# serial_max232.net
KiCad netlist of a schematic drawn in EAGLE
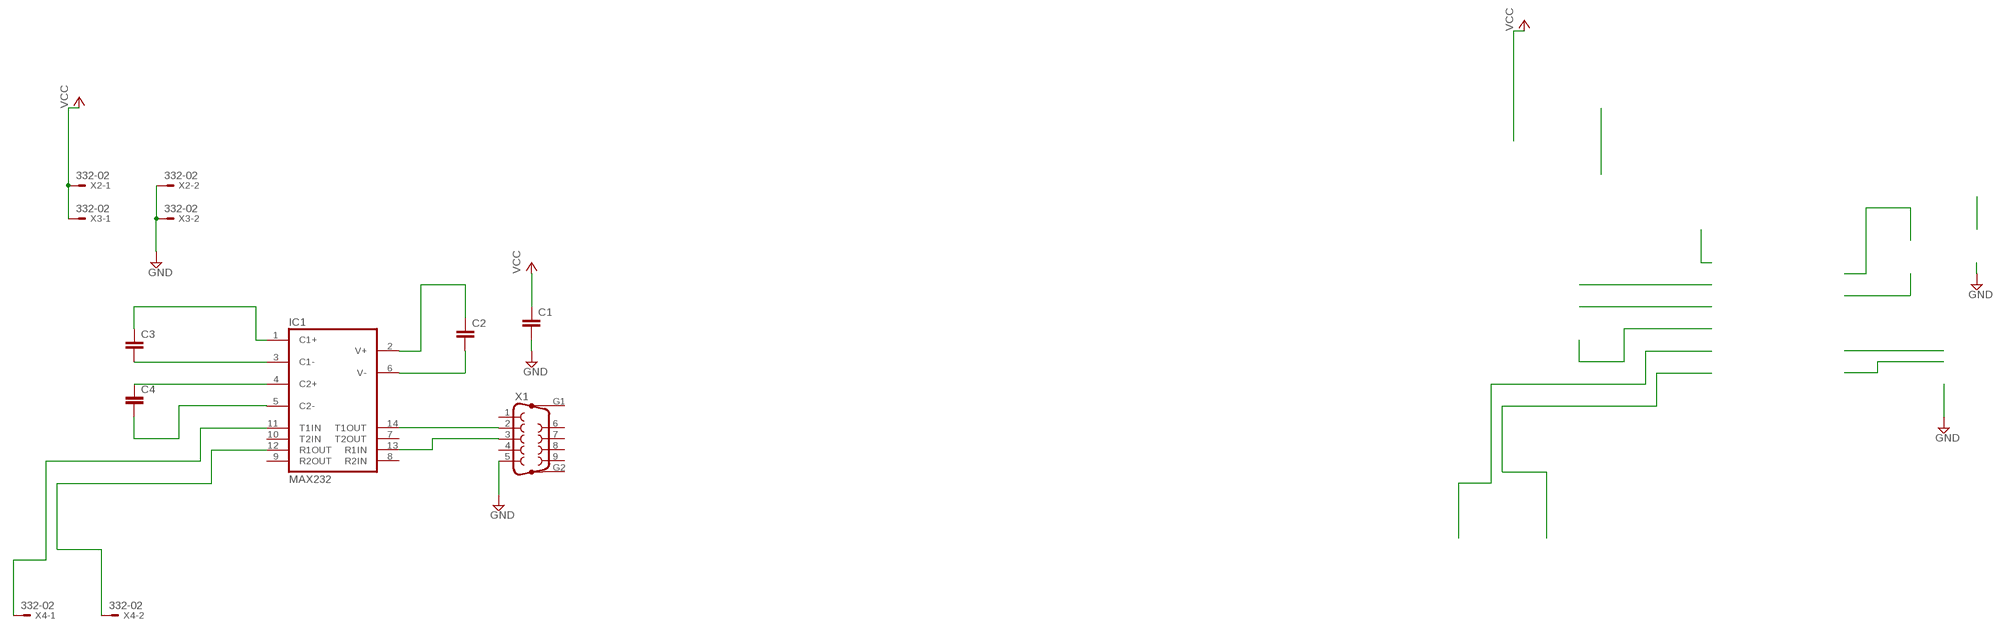
[diagram p0: schematic, sheet 1]

(export (version "E")
  (design (tool "Eeschema 10.0.6"))
  (components
    (comp (ref "C1")
      (value "C5/7.2")
      (footprint "eagle-import:C5B7.2")
      (libsource (lib "eagle-import") (part "C5/7.2"))
    )
    (comp (ref "C2")
      (value "C5/7.2")
      (footprint "eagle-import:C5B7.2")
      (libsource (lib "eagle-import") (part "C5/7.2"))
    )
    (comp (ref "C3")
      (value "C5/7.2")
      (footprint "eagle-import:C5B7.2")
      (libsource (lib "eagle-import") (part "C5/7.2"))
    )
    (comp (ref "C4")
      (value "C5/7.2")
      (footprint "eagle-import:C5B7.2")
      (libsource (lib "eagle-import") (part "C5/7.2"))
    )
    (comp (ref "IC1")
      (value "MAX232")
      (footprint "eagle-import:DIL16")
      (fields (field (name "MF") "MAXIM") (field (name "MPN") "MAX232ACPE+"))
      (libsource (lib "eagle-import") (part "MAX232"))
    )
    (comp (ref "X1")
      (value "F09VP")
      (footprint "eagle-import:F09VP")
      (libsource (lib "eagle-import") (part "F09VP"))
    )
    (comp (ref "X2")
      (value "332-02")
      (footprint "eagle-import:332-02")
      (libsource (lib "eagle-import") (part "332-02"))
    )
    (comp (ref "X3")
      (value "332-02")
      (footprint "eagle-import:332-02")
      (libsource (lib "eagle-import") (part "332-02"))
    )
    (comp (ref "X4")
      (value "332-02")
      (footprint "eagle-import:332-02")
      (libsource (lib "eagle-import") (part "332-02"))
    )
  )
  (nets
    (net (code "1") (name "GND") (class "Default")
      (node (ref "C1") (pin "2") (pinfunction "2_2") (pintype "passive"))
      (node (ref "X1") (pin "5") (pinfunction "5_5") (pintype "passive"))
      (node (ref "X2") (pin "2") (pinfunction "S_2") (pintype "passive"))
      (node (ref "X3") (pin "2") (pinfunction "S_2") (pintype "passive"))
    )
    (net (code "2") (name "Net-(IC1A-C1+)") (class "Default")
      (node (ref "C3") (pin "1") (pinfunction "1_1") (pintype "passive"))
      (node (ref "IC1") (pin "1") (pinfunction "C1+_1") (pintype "bidirectional"))
    )
    (net (code "3") (name "Net-(IC1A-C1-)") (class "Default")
      (node (ref "C3") (pin "2") (pinfunction "2_2") (pintype "passive"))
      (node (ref "IC1") (pin "3") (pinfunction "C1-_3") (pintype "bidirectional"))
    )
    (net (code "4") (name "Net-(IC1A-C2+)") (class "Default")
      (node (ref "C4") (pin "1") (pinfunction "1_1") (pintype "passive"))
      (node (ref "IC1") (pin "4") (pinfunction "C2+_4") (pintype "bidirectional"))
    )
    (net (code "5") (name "Net-(IC1A-C2-)") (class "Default")
      (node (ref "C4") (pin "2") (pinfunction "2_2") (pintype "passive"))
      (node (ref "IC1") (pin "5") (pinfunction "C2-_5") (pintype "bidirectional"))
    )
    (net (code "6") (name "Net-(IC1A-R1IN)") (class "Default")
      (node (ref "IC1") (pin "13") (pinfunction "R1IN_13") (pintype "input"))
      (node (ref "X1") (pin "3") (pinfunction "3_3") (pintype "passive"))
    )
    (net (code "7") (name "Net-(IC1A-R1OUT)") (class "Default")
      (node (ref "IC1") (pin "12") (pinfunction "R1OUT_12") (pintype "output"))
      (node (ref "X4") (pin "2") (pinfunction "S_2") (pintype "passive"))
    )
    (net (code "8") (name "Net-(IC1A-T1IN)") (class "Default")
      (node (ref "IC1") (pin "11") (pinfunction "T1IN_11") (pintype "input"))
      (node (ref "X4") (pin "1") (pinfunction "S_1") (pintype "passive"))
    )
    (net (code "9") (name "Net-(IC1A-T1OUT)") (class "Default")
      (node (ref "IC1") (pin "14") (pinfunction "T1OUT_14") (pintype "output"))
      (node (ref "X1") (pin "2") (pinfunction "2_2") (pintype "passive"))
    )
    (net (code "10") (name "Net-(IC1A-V+)") (class "Default")
      (node (ref "C2") (pin "1") (pinfunction "1_1") (pintype "passive"))
      (node (ref "IC1") (pin "2") (pinfunction "V+_2") (pintype "bidirectional"))
    )
    (net (code "11") (name "Net-(IC1A-V-)") (class "Default")
      (node (ref "C2") (pin "2") (pinfunction "2_2") (pintype "passive"))
      (node (ref "IC1") (pin "6") (pinfunction "V-_6") (pintype "bidirectional"))
    )
    (net (code "12") (name "VCC") (class "Default")
      (node (ref "C1") (pin "1") (pinfunction "1_1") (pintype "passive"))
      (node (ref "X2") (pin "1") (pinfunction "S_1") (pintype "passive"))
      (node (ref "X3") (pin "1") (pinfunction "S_1") (pintype "passive"))
    )
    (net (code "13") (name "unconnected-(IC1A-R2IN-Pad8)") (class "Default")
      (node (ref "IC1") (pin "8") (pinfunction "R2IN_8") (pintype "input"))
    )
    (net (code "14") (name "unconnected-(IC1A-R2OUT-Pad9)") (class "Default")
      (node (ref "IC1") (pin "9") (pinfunction "R2OUT_9") (pintype "output"))
    )
    (net (code "15") (name "unconnected-(IC1A-T2IN-Pad10)") (class "Default")
      (node (ref "IC1") (pin "10") (pinfunction "T2IN_10") (pintype "input"))
    )
    (net (code "16") (name "unconnected-(IC1A-T2OUT-Pad7)") (class "Default")
      (node (ref "IC1") (pin "7") (pinfunction "T2OUT_7") (pintype "output"))
    )
    (net (code "17") (name "unconnected-(X1-Pad1)") (class "Default")
      (node (ref "X1") (pin "1") (pinfunction "1_1") (pintype "passive"))
    )
    (net (code "18") (name "unconnected-(X1-Pad4)") (class "Default")
      (node (ref "X1") (pin "4") (pinfunction "4_4") (pintype "passive"))
    )
    (net (code "19") (name "unconnected-(X1-Pad6)") (class "Default")
      (node (ref "X1") (pin "6") (pinfunction "6_6") (pintype "passive"))
    )
    (net (code "20") (name "unconnected-(X1-Pad7)") (class "Default")
      (node (ref "X1") (pin "7") (pinfunction "7_7") (pintype "passive"))
    )
    (net (code "21") (name "unconnected-(X1-Pad8)") (class "Default")
      (node (ref "X1") (pin "8") (pinfunction "8_8") (pintype "passive"))
    )
    (net (code "22") (name "unconnected-(X1-Pad9)") (class "Default")
      (node (ref "X1") (pin "9") (pinfunction "9_9") (pintype "passive"))
    )
    (net (code "23") (name "unconnected-(X1-PadG1)") (class "Default")
      (node (ref "X1") (pin "G1") (pinfunction "G1_G1") (pintype "passive"))
    )
    (net (code "24") (name "unconnected-(X1-PadG2)") (class "Default")
      (node (ref "X1") (pin "G2") (pinfunction "G2_G2") (pintype "passive"))
    )
  )
)
